# Angin_Arus_LM2596.net
KiCad netlist of a schematic drawn in EAGLE
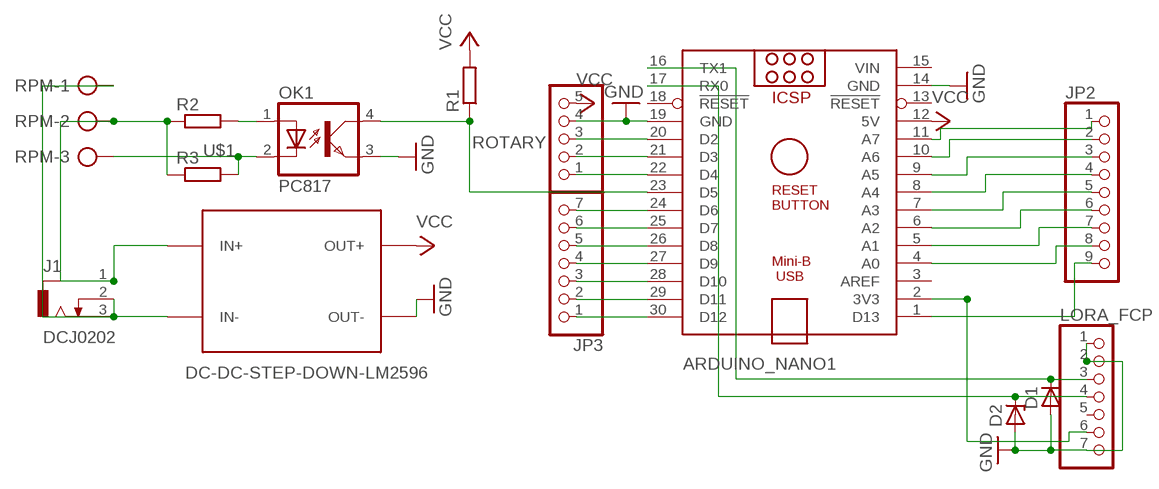
[diagram p0: schematic, sheet 1]

(export (version "E")
  (design (tool "Eeschema 10.0.6"))
  (components
    (comp (ref "ARDUINO_NANO1")
      (value "ARDUINO_NANO")
      (footprint "eagle-import:ARDUINO_NANO")
      (libsource (lib "eagle-import") (part "ARDUINO_NANO"))
    )
    (comp (ref "D1")
      (value "ZENER-DIODEDO35Z10")
      (footprint "eagle-import:DO35Z10")
      (libsource (lib "eagle-import") (part "ZENER-DIODEDO35Z10"))
    )
    (comp (ref "D2")
      (value "ZENER-DIODEDO35Z10")
      (footprint "eagle-import:DO35Z10")
      (libsource (lib "eagle-import") (part "ZENER-DIODEDO35Z10"))
    )
    (comp (ref "J1")
      (value "DCJ0202")
      (footprint "eagle-import:DCJ0202")
      (libsource (lib "eagle-import") (part "DCJ0202"))
    )
    (comp (ref "JP2")
      (value "PINHD-1X9")
      (footprint "eagle-import:1X09")
      (libsource (lib "eagle-import") (part "PINHD-1X9"))
    )
    (comp (ref "JP3")
      (value "PINHD-1X7")
      (footprint "eagle-import:1X07")
      (libsource (lib "eagle-import") (part "PINHD-1X7"))
    )
    (comp (ref "LORA_FCP")
      (value "PINHD-1X7")
      (footprint "eagle-import:1X07")
      (libsource (lib "eagle-import") (part "PINHD-1X7"))
    )
    (comp (ref "OK1")
      (value "PC817")
      (footprint "eagle-import:DIL04")
      (fields (field (name "MPN") "PC817X4J000F"))
      (libsource (lib "eagle-import") (part "PC817"))
    )
    (comp (ref "R1")
      (value "R-EU_0204/7")
      (footprint "eagle-import:0204_7")
      (libsource (lib "eagle-import") (part "R-EU_0204/7"))
    )
    (comp (ref "R2")
      (value "R-EU_0204/7")
      (footprint "eagle-import:0204_7")
      (libsource (lib "eagle-import") (part "R-EU_0204/7"))
    )
    (comp (ref "R3")
      (value "R-EU_0204/7")
      (footprint "eagle-import:0204_7")
      (libsource (lib "eagle-import") (part "R-EU_0204/7"))
    )
    (comp (ref "ROTARY")
      (value "PINHD-1X5")
      (footprint "eagle-import:1X05")
      (libsource (lib "eagle-import") (part "PINHD-1X5"))
    )
    (comp (ref "RPM")
      (value "AK300/3")
      (footprint "eagle-import:AK300_3")
      (libsource (lib "eagle-import") (part "AK300/3"))
    )
    (comp (ref "U$1")
      (value "DC-DC-STEP-DOWN-LM2596")
      (footprint "eagle-import:DC-DC-STEP-DOWN-LM2596")
      (libsource (lib "eagle-import") (part "DC-DC-STEP-DOWN-LM2596"))
    )
  )
  (nets
    (net (code "1") (name "/VIN") (class "Default")
      (node (ref "ARDUINO_NANO1") (pin "15") (pinfunction "VIN_15") (pintype "power_in"))
    )
    (net (code "2") (name "GND") (class "Default")
      (node (ref "ARDUINO_NANO1") (pin "14") (pinfunction "GND_14") (pintype "power_in"))
      (node (ref "ARDUINO_NANO1") (pin "19") (pinfunction "GND_19") (pintype "power_in"))
      (node (ref "D1") (pin "A") (pinfunction "A_A") (pintype "passive"))
      (node (ref "D2") (pin "A") (pinfunction "A_A") (pintype "passive"))
      (node (ref "LORA_FCP") (pin "1") (pinfunction "1_1") (pintype "passive"))
      (node (ref "LORA_FCP") (pin "2") (pinfunction "2_2") (pintype "passive"))
      (node (ref "LORA_FCP") (pin "7") (pinfunction "7_7") (pintype "passive"))
      (node (ref "OK1") (pin "3") (pinfunction "EMIT_3") (pintype "passive"))
      (node (ref "ROTARY") (pin "4") (pinfunction "4_4") (pintype "passive"))
      (node (ref "U$1") (pin "OUT-") (pinfunction "OUT-_OUT-") (pintype "bidirectional"))
    )
    (net (code "3") (name "Net-(ARDUINO_NANO1-3V3)") (class "Default")
      (node (ref "ARDUINO_NANO1") (pin "2") (pinfunction "3V3_2") (pintype "output"))
      (node (ref "LORA_FCP") (pin "6") (pinfunction "6_6") (pintype "passive"))
    )
    (net (code "4") (name "Net-(ARDUINO_NANO1-A0)") (class "Default")
      (node (ref "ARDUINO_NANO1") (pin "4") (pinfunction "A0_4") (pintype "bidirectional"))
      (node (ref "JP2") (pin "8") (pinfunction "8_8") (pintype "passive"))
    )
    (net (code "5") (name "Net-(ARDUINO_NANO1-A1)") (class "Default")
      (node (ref "ARDUINO_NANO1") (pin "5") (pinfunction "A1_5") (pintype "bidirectional"))
      (node (ref "JP2") (pin "7") (pinfunction "7_7") (pintype "passive"))
    )
    (net (code "6") (name "Net-(ARDUINO_NANO1-A2)") (class "Default")
      (node (ref "ARDUINO_NANO1") (pin "6") (pinfunction "A2_6") (pintype "bidirectional"))
      (node (ref "JP2") (pin "6") (pinfunction "6_6") (pintype "passive"))
    )
    (net (code "7") (name "Net-(ARDUINO_NANO1-A3)") (class "Default")
      (node (ref "ARDUINO_NANO1") (pin "7") (pinfunction "A3_7") (pintype "bidirectional"))
      (node (ref "JP2") (pin "5") (pinfunction "5_5") (pintype "passive"))
    )
    (net (code "8") (name "Net-(ARDUINO_NANO1-A4)") (class "Default")
      (node (ref "ARDUINO_NANO1") (pin "8") (pinfunction "A4_8") (pintype "bidirectional"))
      (node (ref "JP2") (pin "4") (pinfunction "4_4") (pintype "passive"))
    )
    (net (code "9") (name "Net-(ARDUINO_NANO1-A5)") (class "Default")
      (node (ref "ARDUINO_NANO1") (pin "9") (pinfunction "A5_9") (pintype "bidirectional"))
      (node (ref "JP2") (pin "3") (pinfunction "3_3") (pintype "passive"))
    )
    (net (code "10") (name "Net-(ARDUINO_NANO1-A6)") (class "Default")
      (node (ref "ARDUINO_NANO1") (pin "10") (pinfunction "A6_10") (pintype "bidirectional"))
      (node (ref "JP2") (pin "2") (pinfunction "2_2") (pintype "passive"))
    )
    (net (code "11") (name "Net-(ARDUINO_NANO1-A7)") (class "Default")
      (node (ref "ARDUINO_NANO1") (pin "11") (pinfunction "A7_11") (pintype "bidirectional"))
      (node (ref "JP2") (pin "1") (pinfunction "1_1") (pintype "passive"))
    )
    (net (code "12") (name "Net-(ARDUINO_NANO1-D2)") (class "Default")
      (node (ref "ARDUINO_NANO1") (pin "20") (pinfunction "D2_20") (pintype "bidirectional"))
      (node (ref "ROTARY") (pin "3") (pinfunction "3_3") (pintype "passive"))
    )
    (net (code "13") (name "Net-(ARDUINO_NANO1-D3)") (class "Default")
      (node (ref "ARDUINO_NANO1") (pin "21") (pinfunction "D3_21") (pintype "bidirectional"))
      (node (ref "ROTARY") (pin "2") (pinfunction "2_2") (pintype "passive"))
    )
    (net (code "14") (name "Net-(ARDUINO_NANO1-D4)") (class "Default")
      (node (ref "ARDUINO_NANO1") (pin "22") (pinfunction "D4_22") (pintype "bidirectional"))
      (node (ref "ROTARY") (pin "1") (pinfunction "1_1") (pintype "passive"))
    )
    (net (code "15") (name "Net-(ARDUINO_NANO1-D5)") (class "Default")
      (node (ref "ARDUINO_NANO1") (pin "23") (pinfunction "D5_23") (pintype "bidirectional"))
      (node (ref "OK1") (pin "4") (pinfunction "COL_4") (pintype "passive"))
      (node (ref "R1") (pin "1") (pinfunction "1_1") (pintype "passive"))
    )
    (net (code "16") (name "Net-(ARDUINO_NANO1-D6)") (class "Default")
      (node (ref "ARDUINO_NANO1") (pin "24") (pinfunction "D6_24") (pintype "bidirectional"))
      (node (ref "JP3") (pin "7") (pinfunction "7_7") (pintype "passive"))
    )
    (net (code "17") (name "Net-(ARDUINO_NANO1-D7)") (class "Default")
      (node (ref "ARDUINO_NANO1") (pin "25") (pinfunction "D7_25") (pintype "bidirectional"))
      (node (ref "JP3") (pin "6") (pinfunction "6_6") (pintype "passive"))
    )
    (net (code "18") (name "Net-(ARDUINO_NANO1-D8)") (class "Default")
      (node (ref "ARDUINO_NANO1") (pin "26") (pinfunction "D8_26") (pintype "bidirectional"))
      (node (ref "JP3") (pin "5") (pinfunction "5_5") (pintype "passive"))
    )
    (net (code "19") (name "Net-(ARDUINO_NANO1-D9)") (class "Default")
      (node (ref "ARDUINO_NANO1") (pin "27") (pinfunction "D9_27") (pintype "bidirectional"))
      (node (ref "JP3") (pin "4") (pinfunction "4_4") (pintype "passive"))
    )
    (net (code "20") (name "Net-(ARDUINO_NANO1-D10)") (class "Default")
      (node (ref "ARDUINO_NANO1") (pin "28") (pinfunction "D10_28") (pintype "bidirectional"))
      (node (ref "JP3") (pin "3") (pinfunction "3_3") (pintype "passive"))
    )
    (net (code "21") (name "Net-(ARDUINO_NANO1-D11)") (class "Default")
      (node (ref "ARDUINO_NANO1") (pin "29") (pinfunction "D11_29") (pintype "bidirectional"))
      (node (ref "JP3") (pin "2") (pinfunction "2_2") (pintype "passive"))
    )
    (net (code "22") (name "Net-(ARDUINO_NANO1-D12)") (class "Default")
      (node (ref "ARDUINO_NANO1") (pin "30") (pinfunction "D12_30") (pintype "bidirectional"))
      (node (ref "JP3") (pin "1") (pinfunction "1_1") (pintype "passive"))
    )
    (net (code "23") (name "Net-(ARDUINO_NANO1-D13)") (class "Default")
      (node (ref "ARDUINO_NANO1") (pin "1") (pinfunction "D13_1") (pintype "bidirectional"))
      (node (ref "JP2") (pin "9") (pinfunction "9_9") (pintype "passive"))
    )
    (net (code "24") (name "Net-(ARDUINO_NANO1-RX0)") (class "Default")
      (node (ref "ARDUINO_NANO1") (pin "17") (pinfunction "RX0_17") (pintype "bidirectional"))
      (node (ref "D2") (pin "C") (pinfunction "C_C") (pintype "passive"))
      (node (ref "LORA_FCP") (pin "4") (pinfunction "4_4") (pintype "passive"))
    )
    (net (code "25") (name "Net-(ARDUINO_NANO1-TX1)") (class "Default")
      (node (ref "ARDUINO_NANO1") (pin "16") (pinfunction "TX1_16") (pintype "bidirectional"))
      (node (ref "D1") (pin "C") (pinfunction "C_C") (pintype "passive"))
      (node (ref "LORA_FCP") (pin "3") (pinfunction "3_3") (pintype "passive"))
    )
    (net (code "26") (name "Net-(OK1-A)") (class "Default")
      (node (ref "OK1") (pin "1") (pinfunction "A_1") (pintype "passive"))
      (node (ref "R2") (pin "2") (pinfunction "2_2") (pintype "passive"))
    )
    (net (code "27") (name "Net-(OK1-C)") (class "Default")
      (node (ref "OK1") (pin "2") (pinfunction "C_2") (pintype "passive"))
      (node (ref "R3") (pin "2") (pinfunction "2_2") (pintype "passive"))
      (node (ref "RPM") (pin "3") (pinfunction "KL_3") (pintype "passive"))
    )
    (net (code "28") (name "Net-(RPMA-KL)") (class "Default")
      (node (ref "J1") (pin "2") (pinfunction "2_2") (pintype "passive"))
      (node (ref "J1") (pin "3") (pinfunction "3_3") (pintype "passive"))
      (node (ref "RPM") (pin "1") (pinfunction "KL_1") (pintype "passive"))
      (node (ref "U$1") (pin "IN-") (pinfunction "IN-_IN-") (pintype "bidirectional"))
    )
    (net (code "29") (name "Net-(RPMB-KL)") (class "Default")
      (node (ref "J1") (pin "1") (pinfunction "1_1") (pintype "passive"))
      (node (ref "R2") (pin "1") (pinfunction "1_1") (pintype "passive"))
      (node (ref "R3") (pin "1") (pinfunction "1_1") (pintype "passive"))
      (node (ref "RPM") (pin "2") (pinfunction "KL_2") (pintype "passive"))
      (node (ref "U$1") (pin "IN+") (pinfunction "IN+_IN+") (pintype "bidirectional"))
    )
    (net (code "30") (name "VCC") (class "Default")
      (node (ref "ARDUINO_NANO1") (pin "12") (pinfunction "5V_12") (pintype "power_in"))
      (node (ref "R1") (pin "2") (pinfunction "2_2") (pintype "passive"))
      (node (ref "ROTARY") (pin "5") (pinfunction "5_5") (pintype "passive"))
      (node (ref "U$1") (pin "OUT+") (pinfunction "OUT+_OUT+") (pintype "bidirectional"))
    )
    (net (code "31") (name "unconnected-(ARDUINO_NANO1-AREF-Pad3)") (class "Default")
      (node (ref "ARDUINO_NANO1") (pin "3") (pinfunction "AREF_3") (pintype "input"))
    )
    (net (code "32") (name "unconnected-(ARDUINO_NANO1-~{RESET}-Pad13)") (class "Default")
      (node (ref "ARDUINO_NANO1") (pin "13") (pinfunction "~{RESET}_13") (pintype "input"))
    )
    (net (code "33") (name "unconnected-(ARDUINO_NANO1-~{RESET}-Pad18)") (class "Default")
      (node (ref "ARDUINO_NANO1") (pin "18") (pinfunction "~{RESET}_18") (pintype "input"))
    )
    (net (code "34") (name "unconnected-(LORA_FCP-Pad5)") (class "Default")
      (node (ref "LORA_FCP") (pin "5") (pinfunction "5_5") (pintype "passive"))
    )
  )
)
